# Sheet.net
KiCad netlist of a schematic drawn in Altium Designer
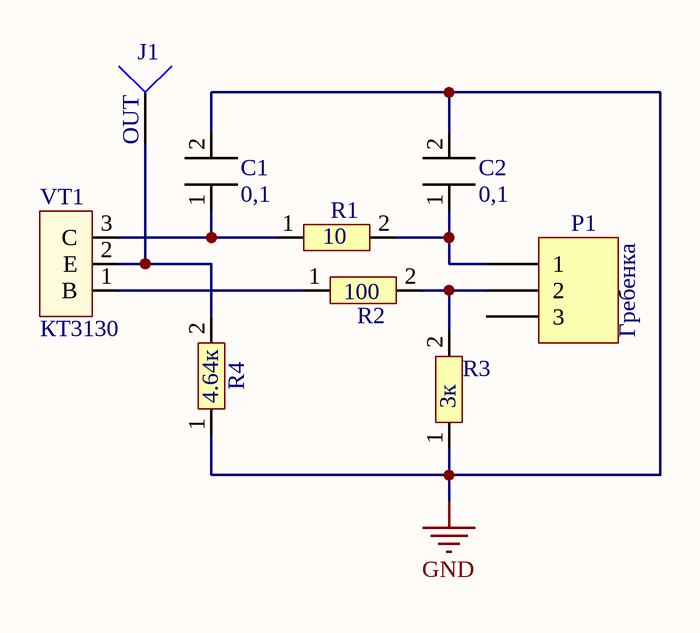
[diagram p0: Sheet.SchDoc]

(export (version "E")
  (design (tool "Eeschema 10.0.6"))
  (components
    (comp (ref "C1") (value "0,1") (footprint "CAP_SMALL") (libsource (lib "Schlib") (part "CAP_SMALL")))
    (comp (ref "C2") (value "0,1") (footprint "CAP_SMALL") (libsource (lib "Schlib") (part "CAP_SMALL")))
    (comp (ref "J1")
      (value "OUT")
      (footprint "PIN1")
      (description "Socket")
      (fields (field (name "PUBLISHER") "Altium Limited"))
      (libsource (lib "Miscellaneous Connectors") (part "Socket"))
    )
    (comp (ref "P1")
      (value "Гребенка")
      (footprint "HDR1X3")
      (description "Header, 3-Pin")
      (fields (field (name "PUBLISHER") "Altium Limited"))
      (libsource (lib "Miscellaneous Connectors") (part "Header 3"))
    )
    (comp (ref "R1") (value "10") (footprint "RES") (libsource (lib "Schlib") (part "RES")))
    (comp (ref "R2") (value "100") (footprint "RES") (libsource (lib "Schlib") (part "RES")))
    (comp (ref "R3") (value "3к") (footprint "RES") (libsource (lib "") (part "RES_1")))
    (comp (ref "R4") (value "4.64к") (footprint "RES") (libsource (lib "") (part "RES_1")))
    (comp (ref "VT1")
      (value "КТ3130")
      (footprint "SOT23-BEC_MMBT3640*(Primary)")
      (libsource (lib "Schlib") (part "MMBT3640"))
    )
  )
  (nets
    (net (code "1") (name "GND") (class "Default")
      (node (ref "C1") (pin "2") (pinfunction "2_2") (pintype "passive"))
      (node (ref "C2") (pin "2") (pinfunction "2_2") (pintype "passive"))
      (node (ref "R3") (pin "1") (pinfunction "1_1") (pintype "passive"))
      (node (ref "R4") (pin "1") (pinfunction "1_1") (pintype "passive"))
    )
    (net (code "2") (name "Net-(C2-Pad1)") (class "Default")
      (node (ref "C2") (pin "1") (pinfunction "1_1") (pintype "passive"))
      (node (ref "P1") (pin "1") (pinfunction "1_1") (pintype "passive"))
      (node (ref "R1") (pin "2") (pinfunction "2_2") (pintype "passive"))
    )
    (net (code "3") (name "Net-(P1-Pad2)") (class "Default")
      (node (ref "P1") (pin "2") (pinfunction "2_2") (pintype "passive"))
      (node (ref "R2") (pin "2") (pinfunction "2_2") (pintype "passive"))
      (node (ref "R3") (pin "2") (pinfunction "2_2") (pintype "passive"))
    )
    (net (code "4") (name "Net-(VT1-B)") (class "Default")
      (node (ref "R2") (pin "1") (pinfunction "1_1") (pintype "passive"))
      (node (ref "VT1") (pin "1") (pinfunction "B_1") (pintype "passive"))
    )
    (net (code "5") (name "Net-(VT1-C)") (class "Default")
      (node (ref "C1") (pin "1") (pinfunction "1_1") (pintype "passive"))
      (node (ref "R1") (pin "1") (pinfunction "1_1") (pintype "passive"))
      (node (ref "VT1") (pin "3") (pinfunction "C_3") (pintype "passive"))
    )
    (net (code "6") (name "Net-(VT1-E)") (class "Default")
      (node (ref "J1") (pin "1") (pinfunction "1_1") (pintype "passive"))
      (node (ref "R4") (pin "2") (pinfunction "2_2") (pintype "passive"))
      (node (ref "VT1") (pin "2") (pinfunction "E_2") (pintype "passive"))
    )
    (net (code "7") (name "unconnected-(P1-Pad3)") (class "Default")
      (node (ref "P1") (pin "3") (pinfunction "3_3") (pintype "passive"))
    )
  )
)
